# Keg_Cop_-_RJ45_-_6-Pack_Tallboy.net
KiCad netlist of a schematic drawn in EAGLE
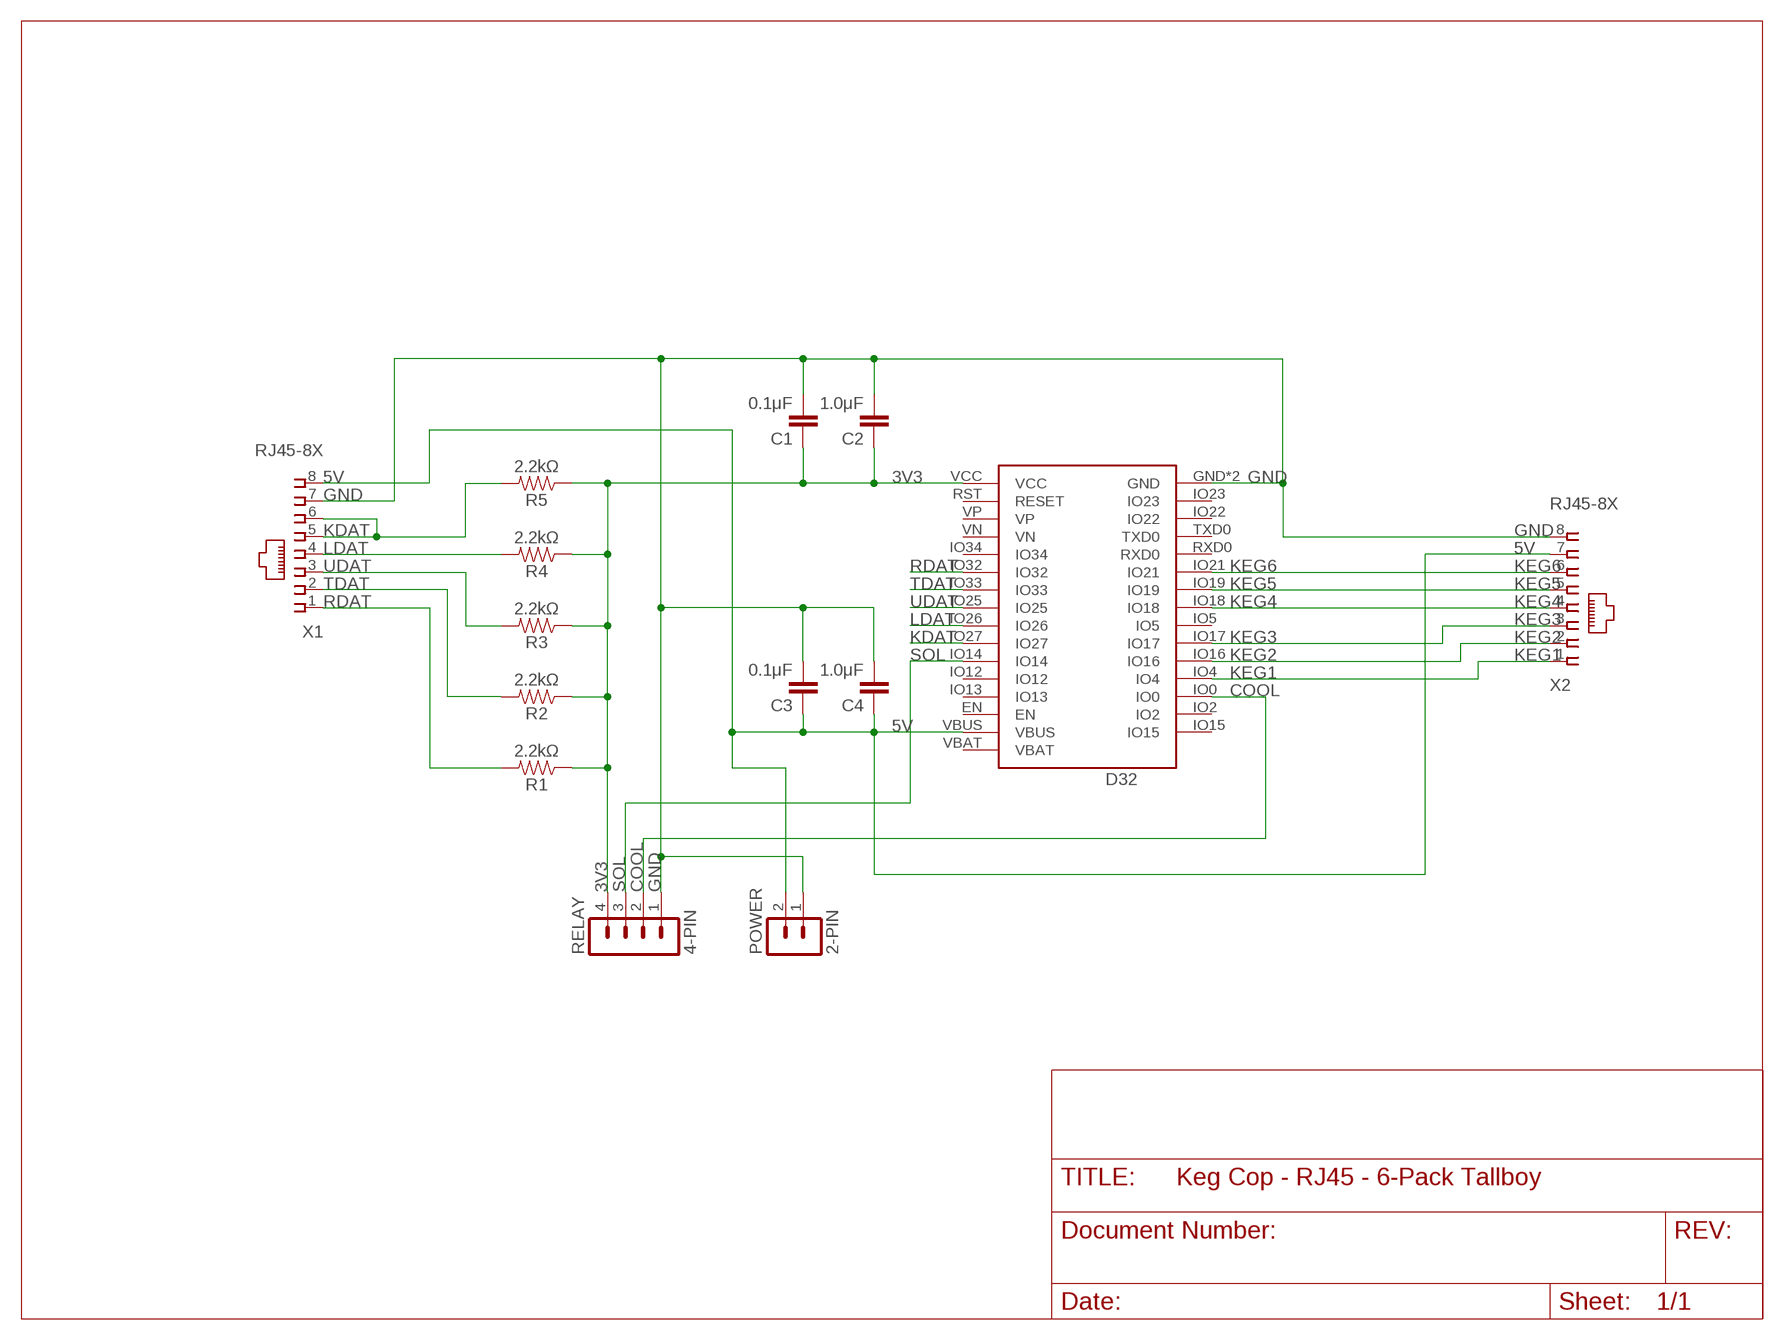
[diagram p0: schematic, sheet 1]

(export (version "E")
  (design (tool "Eeschema 10.0.6"))
  (components
    (comp (ref "C1")
      (value "0.1μF")
      (footprint "eagle-import:CAP_PTH-2.54")
      (libsource (lib "eagle-import") (part "CAP_CERAMIC_2.54"))
    )
    (comp (ref "C2")
      (value "1.0μF")
      (footprint "eagle-import:CAP_PTH-2.54")
      (libsource (lib "eagle-import") (part "CAP_CERAMIC_2.54"))
    )
    (comp (ref "C3")
      (value "0.1μF")
      (footprint "eagle-import:CAP_PTH-2.54")
      (libsource (lib "eagle-import") (part "CAP_CERAMIC_2.54"))
    )
    (comp (ref "C4")
      (value "1.0μF")
      (footprint "eagle-import:CAP_PTH-2.54")
      (libsource (lib "eagle-import") (part "CAP_CERAMIC_2.54"))
    )
    (comp (ref "D32")
      (value "Lolin D32")
      (footprint "eagle-import:D32_NO_BATT")
      (libsource (lib "eagle-import") (part "WEMOS-D32D32_NO_BATT"))
    )
    (comp (ref "POWER")
      (value "2-PIN")
      (footprint "eagle-import:HDR-2_VERT")
      (libsource (lib "eagle-import") (part "HDR-2"))
    )
    (comp (ref "R1")
      (value "2.2kΩ")
      (footprint "eagle-import:AXIAL-0.3")
      (libsource (lib "eagle-import") (part "RESISTORAXIAL-0.3"))
    )
    (comp (ref "R2")
      (value "2.2kΩ")
      (footprint "eagle-import:AXIAL-0.3")
      (libsource (lib "eagle-import") (part "RESISTORAXIAL-0.3"))
    )
    (comp (ref "R3")
      (value "2.2kΩ")
      (footprint "eagle-import:AXIAL-0.3")
      (libsource (lib "eagle-import") (part "RESISTORAXIAL-0.3"))
    )
    (comp (ref "R4")
      (value "2.2kΩ")
      (footprint "eagle-import:AXIAL-0.3")
      (libsource (lib "eagle-import") (part "RESISTORAXIAL-0.3"))
    )
    (comp (ref "R5")
      (value "2.2kΩ")
      (footprint "eagle-import:AXIAL-0.3")
      (libsource (lib "eagle-import") (part "RESISTORAXIAL-0.3"))
    )
    (comp (ref "RELAY")
      (value "4-PIN")
      (footprint "eagle-import:MA04-1")
      (libsource (lib "eagle-import") (part "MA04-1"))
    )
    (comp (ref "X1")
      (value "RJ45-8X")
      (footprint "eagle-import:RJ45-NO-SHIELD")
      (libsource (lib "eagle-import") (part "RJ45-8X"))
    )
    (comp (ref "X2")
      (value "RJ45-8X")
      (footprint "eagle-import:RJ45-NO-SHIELD")
      (libsource (lib "eagle-import") (part "RJ45-8X"))
    )
  )
  (nets
    (net (code "1") (name "/3V3") (class "Default")
      (node (ref "C1") (pin "1") (pinfunction "1_1") (pintype "passive"))
      (node (ref "C2") (pin "1") (pinfunction "1_1") (pintype "passive"))
      (node (ref "D32") (pin "VCC") (pinfunction "VCC_VCC") (pintype "power_in"))
      (node (ref "R1") (pin "P$1") (pinfunction "1_P$1") (pintype "passive"))
      (node (ref "R2") (pin "P$1") (pinfunction "1_P$1") (pintype "passive"))
      (node (ref "R3") (pin "P$1") (pinfunction "1_P$1") (pintype "passive"))
      (node (ref "R4") (pin "P$1") (pinfunction "1_P$1") (pintype "passive"))
      (node (ref "R5") (pin "P$1") (pinfunction "1_P$1") (pintype "passive"))
      (node (ref "RELAY") (pin "4") (pinfunction "4_4") (pintype "passive"))
    )
    (net (code "2") (name "/5V") (class "Default")
      (node (ref "C3") (pin "1") (pinfunction "1_1") (pintype "passive"))
      (node (ref "C4") (pin "1") (pinfunction "1_1") (pintype "passive"))
      (node (ref "D32") (pin "VBUS") (pinfunction "VBUS_VBUS") (pintype "bidirectional"))
      (node (ref "POWER") (pin "2") (pinfunction "2_2") (pintype "passive"))
      (node (ref "X1") (pin "8") (pinfunction "8_8") (pintype "passive"))
      (node (ref "X2") (pin "7") (pinfunction "7_7") (pintype "passive"))
    )
    (net (code "3") (name "/COOL") (class "Default")
      (node (ref "D32") (pin "IO0") (pinfunction "IO0_IO0") (pintype "bidirectional"))
      (node (ref "RELAY") (pin "2") (pinfunction "2_2") (pintype "passive"))
    )
    (net (code "4") (name "/GND") (class "Default")
      (node (ref "C1") (pin "2") (pinfunction "2_2") (pintype "passive"))
      (node (ref "C2") (pin "2") (pinfunction "2_2") (pintype "passive"))
      (node (ref "C3") (pin "2") (pinfunction "2_2") (pintype "passive"))
      (node (ref "C4") (pin "2") (pinfunction "2_2") (pintype "passive"))
      (node (ref "D32") (pin "GND") (pinfunction "GND_GND") (pintype "power_in"))
      (node (ref "D32") (pin "GND2") (pinfunction "GND_GND2") (pintype "power_in"))
      (node (ref "POWER") (pin "1") (pinfunction "1_1") (pintype "passive"))
      (node (ref "RELAY") (pin "1") (pinfunction "1_1") (pintype "passive"))
      (node (ref "X1") (pin "7") (pinfunction "7_7") (pintype "passive"))
      (node (ref "X2") (pin "8") (pinfunction "8_8") (pintype "passive"))
    )
    (net (code "5") (name "/KDAT") (class "Default")
      (node (ref "D32") (pin "IO27") (pinfunction "IO27_IO27") (pintype "bidirectional"))
      (node (ref "R5") (pin "P$2") (pinfunction "2_P$2") (pintype "passive"))
      (node (ref "X1") (pin "5") (pinfunction "5_5") (pintype "passive"))
      (node (ref "X1") (pin "6") (pinfunction "6_6") (pintype "passive"))
    )
    (net (code "6") (name "/KEG1") (class "Default")
      (node (ref "D32") (pin "IO4") (pinfunction "IO4_IO4") (pintype "bidirectional"))
      (node (ref "X2") (pin "1") (pinfunction "1_1") (pintype "passive"))
    )
    (net (code "7") (name "/KEG2") (class "Default")
      (node (ref "D32") (pin "IO16") (pinfunction "IO16_IO16") (pintype "bidirectional"))
      (node (ref "X2") (pin "2") (pinfunction "2_2") (pintype "passive"))
    )
    (net (code "8") (name "/KEG3") (class "Default")
      (node (ref "D32") (pin "IO17") (pinfunction "IO17_IO17") (pintype "bidirectional"))
      (node (ref "X2") (pin "3") (pinfunction "3_3") (pintype "passive"))
    )
    (net (code "9") (name "/KEG4") (class "Default")
      (node (ref "D32") (pin "IO18") (pinfunction "IO18_IO18") (pintype "bidirectional"))
      (node (ref "X2") (pin "4") (pinfunction "4_4") (pintype "passive"))
    )
    (net (code "10") (name "/KEG5") (class "Default")
      (node (ref "D32") (pin "IO19") (pinfunction "IO19_IO19") (pintype "bidirectional"))
      (node (ref "X2") (pin "5") (pinfunction "5_5") (pintype "passive"))
    )
    (net (code "11") (name "/KEG6") (class "Default")
      (node (ref "D32") (pin "IO21") (pinfunction "IO21_IO21") (pintype "bidirectional"))
      (node (ref "X2") (pin "6") (pinfunction "6_6") (pintype "passive"))
    )
    (net (code "12") (name "/LDAT") (class "Default")
      (node (ref "D32") (pin "IO26") (pinfunction "IO26_IO26") (pintype "bidirectional"))
      (node (ref "R4") (pin "P$2") (pinfunction "2_P$2") (pintype "passive"))
      (node (ref "X1") (pin "4") (pinfunction "4_4") (pintype "passive"))
    )
    (net (code "13") (name "/RDAT") (class "Default")
      (node (ref "D32") (pin "IO32") (pinfunction "IO32_IO32") (pintype "bidirectional"))
      (node (ref "R1") (pin "P$2") (pinfunction "2_P$2") (pintype "passive"))
      (node (ref "X1") (pin "1") (pinfunction "1_1") (pintype "passive"))
    )
    (net (code "14") (name "/SOL") (class "Default")
      (node (ref "D32") (pin "IO14") (pinfunction "IO14_IO14") (pintype "bidirectional"))
      (node (ref "RELAY") (pin "3") (pinfunction "3_3") (pintype "passive"))
    )
    (net (code "15") (name "/TDAT") (class "Default")
      (node (ref "D32") (pin "IO33") (pinfunction "IO33_IO33") (pintype "bidirectional"))
      (node (ref "R2") (pin "P$2") (pinfunction "2_P$2") (pintype "passive"))
      (node (ref "X1") (pin "2") (pinfunction "2_2") (pintype "passive"))
    )
    (net (code "16") (name "/UDAT") (class "Default")
      (node (ref "D32") (pin "IO25") (pinfunction "IO25_IO25") (pintype "bidirectional"))
      (node (ref "R3") (pin "P$2") (pinfunction "2_P$2") (pintype "passive"))
      (node (ref "X1") (pin "3") (pinfunction "3_3") (pintype "passive"))
    )
    (net (code "17") (name "unconnected-(D32-PadEN)") (class "Default")
      (node (ref "D32") (pin "EN") (pinfunction "EN_EN") (pintype "bidirectional"))
    )
    (net (code "18") (name "unconnected-(D32-PadIO2)") (class "Default")
      (node (ref "D32") (pin "IO2") (pinfunction "IO2_IO2") (pintype "bidirectional"))
    )
    (net (code "19") (name "unconnected-(D32-PadIO5)") (class "Default")
      (node (ref "D32") (pin "IO5") (pinfunction "IO5_IO5") (pintype "bidirectional"))
    )
    (net (code "20") (name "unconnected-(D32-PadIO12)") (class "Default")
      (node (ref "D32") (pin "IO12") (pinfunction "IO12_IO12") (pintype "bidirectional"))
    )
    (net (code "21") (name "unconnected-(D32-PadIO13)") (class "Default")
      (node (ref "D32") (pin "IO13") (pinfunction "IO13_IO13") (pintype "bidirectional"))
    )
    (net (code "22") (name "unconnected-(D32-PadIO15)") (class "Default")
      (node (ref "D32") (pin "IO15") (pinfunction "IO15_IO15") (pintype "bidirectional"))
    )
    (net (code "23") (name "unconnected-(D32-PadIO22)") (class "Default")
      (node (ref "D32") (pin "IO22") (pinfunction "IO22_IO22") (pintype "bidirectional"))
    )
    (net (code "24") (name "unconnected-(D32-PadIO23)") (class "Default")
      (node (ref "D32") (pin "IO23") (pinfunction "IO23_IO23") (pintype "bidirectional"))
    )
    (net (code "25") (name "unconnected-(D32-PadIO34)") (class "Default")
      (node (ref "D32") (pin "IO34") (pinfunction "IO34_IO34") (pintype "bidirectional"))
    )
    (net (code "26") (name "unconnected-(D32-PadRXD0)") (class "Default")
      (node (ref "D32") (pin "RXD0") (pinfunction "RXD0_RXD0") (pintype "input"))
    )
    (net (code "27") (name "unconnected-(D32-PadTXD0)") (class "Default")
      (node (ref "D32") (pin "TXD0") (pinfunction "TXD0_TXD0") (pintype "output"))
    )
    (net (code "28") (name "unconnected-(D32-PadVBAT)") (class "Default")
      (node (ref "D32") (pin "VBAT") (pinfunction "VBAT_VBAT") (pintype "bidirectional"))
    )
    (net (code "29") (name "unconnected-(D32-PadVN)") (class "Default")
      (node (ref "D32") (pin "VN") (pinfunction "VN_VN") (pintype "bidirectional"))
    )
    (net (code "30") (name "unconnected-(D32-PadVP)") (class "Default")
      (node (ref "D32") (pin "VP") (pinfunction "VP_VP") (pintype "bidirectional"))
    )
    (net (code "31") (name "unconnected-(D32-RESET-PadRST)") (class "Default")
      (node (ref "D32") (pin "RST") (pinfunction "RESET_RST") (pintype "bidirectional"))
    )
  )
)
